# PCB-VU-SE-2.net
KiCad netlist of a schematic drawn in EAGLE
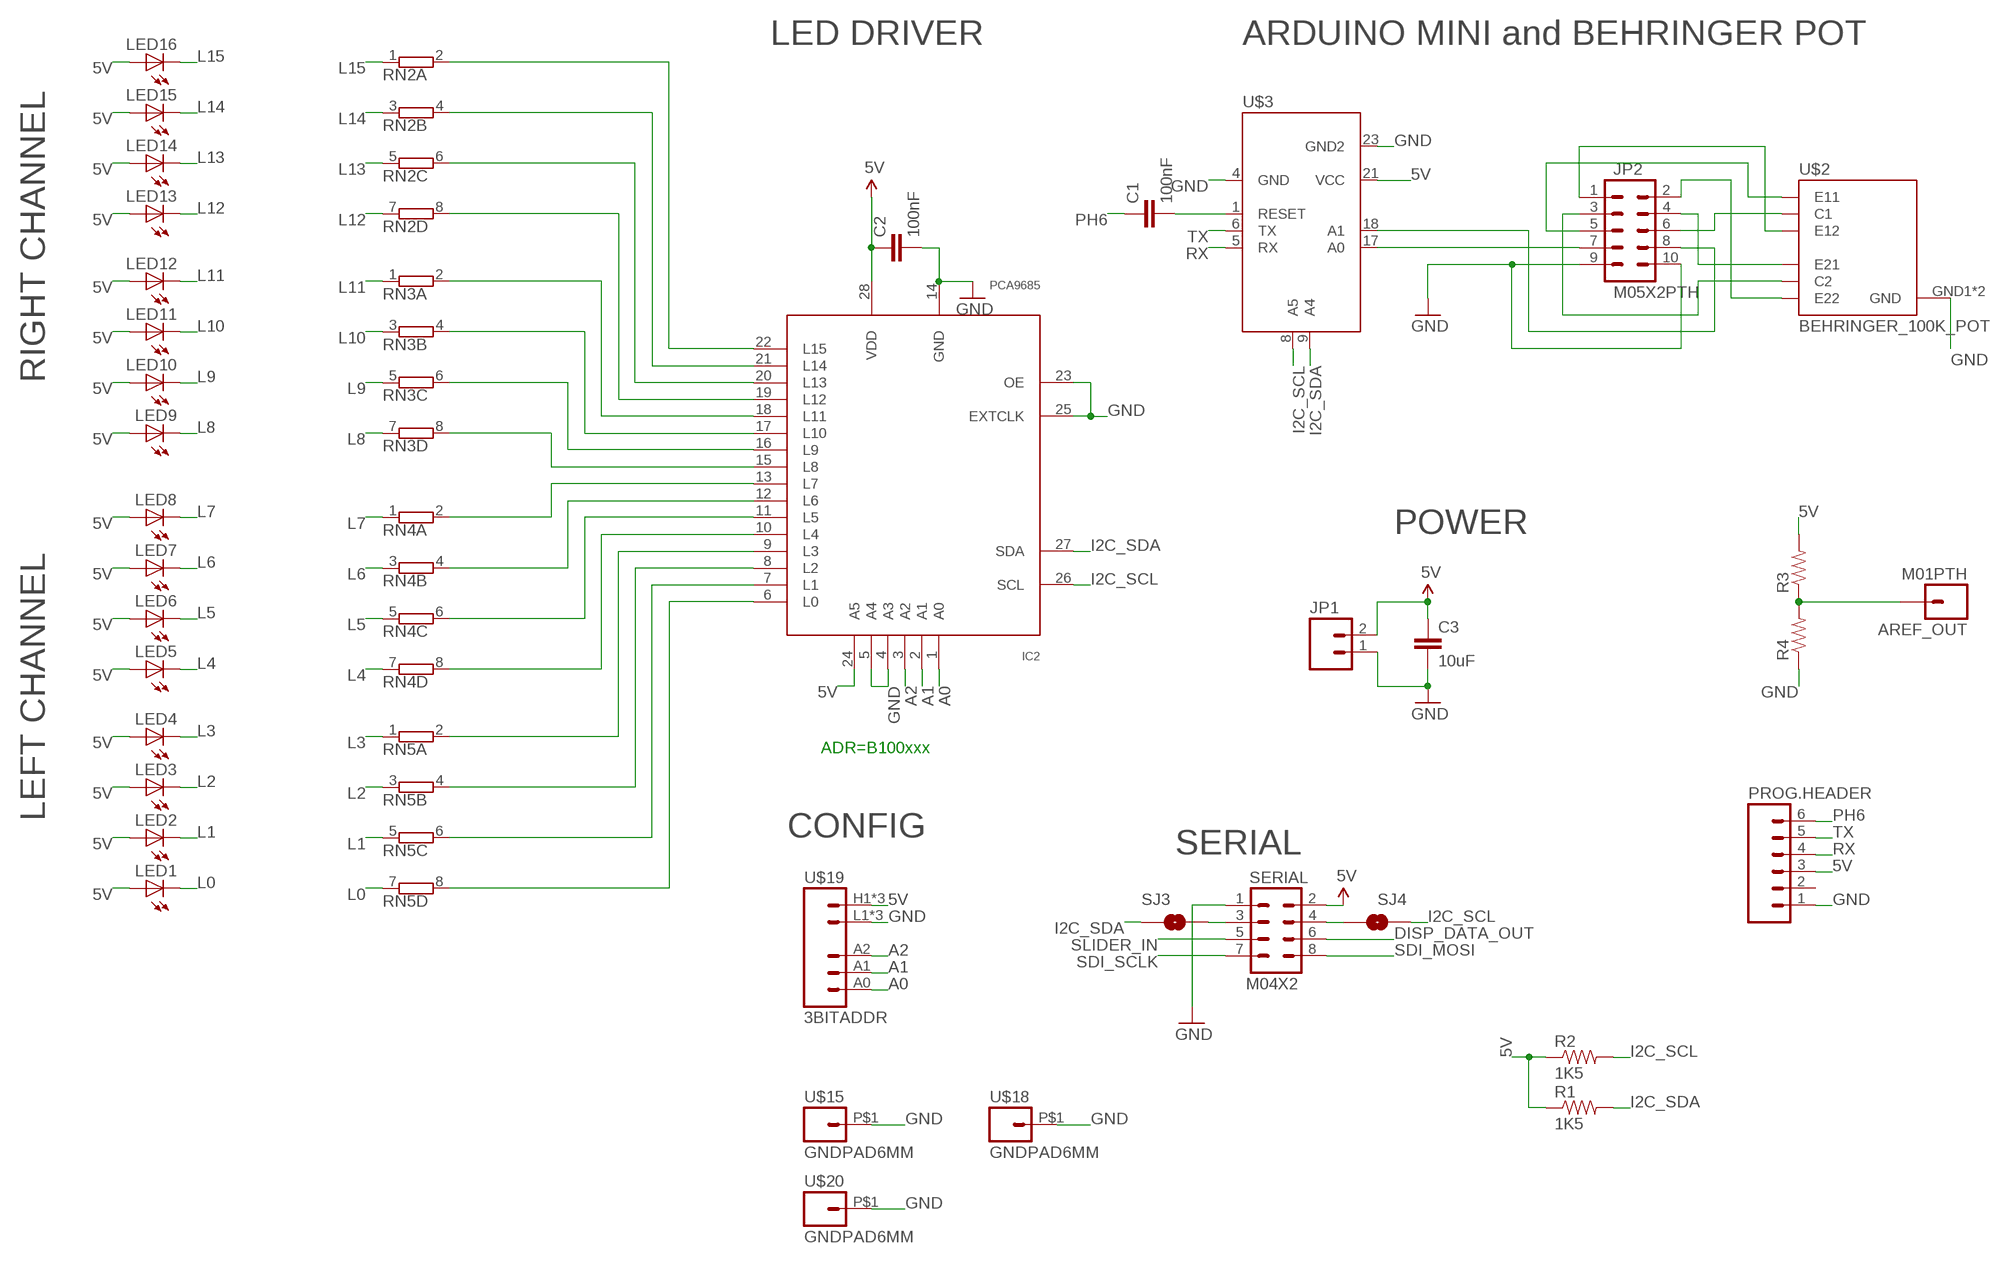
[diagram p0: schematic, sheet 1]

(export (version "E")
  (design (tool "Eeschema 10.0.6"))
  (components
    (comp (ref "AREF_OUT")
      (value "M01PTH")
      (footprint "eagle-import:1X01")
      (libsource (lib "eagle-import") (part "M01PTH"))
    )
    (comp (ref "C1")
      (value "100nF")
      (footprint "eagle-import:0603-CAP")
      (libsource (lib "eagle-import") (part "CAP0603-CAP"))
    )
    (comp (ref "C2")
      (value "100nF")
      (footprint "eagle-import:0603-CAP")
      (libsource (lib "eagle-import") (part "CAP0603-CAP"))
    )
    (comp (ref "C3")
      (value "10uF")
      (footprint "eagle-import:0805")
      (libsource (lib "eagle-import") (part "CAP0805"))
    )
    (comp (ref "IC2")
      (value "PCA9685")
      (footprint "eagle-import:TSSOP28")
      (libsource (lib "eagle-import") (part "PCA9685"))
    )
    (comp (ref "JP1")
      (value "M02PTH")
      (footprint "eagle-import:1X02")
      (libsource (lib "eagle-import") (part "M02PTH"))
    )
    (comp (ref "JP2")
      (value "M05X2PTH")
      (footprint "eagle-import:AVR_ICSP")
      (libsource (lib "eagle-import") (part "M05X2PTH"))
    )
    (comp (ref "LED1")
      (value "LED3MM")
      (footprint "eagle-import:LED3MM")
      (libsource (lib "eagle-import") (part "LED3MM"))
    )
    (comp (ref "LED2")
      (value "LED3MM")
      (footprint "eagle-import:LED3MM")
      (libsource (lib "eagle-import") (part "LED3MM"))
    )
    (comp (ref "LED3")
      (value "LED3MM")
      (footprint "eagle-import:LED3MM")
      (libsource (lib "eagle-import") (part "LED3MM"))
    )
    (comp (ref "LED4")
      (value "LED3MM")
      (footprint "eagle-import:LED3MM")
      (libsource (lib "eagle-import") (part "LED3MM"))
    )
    (comp (ref "LED5")
      (value "LED3MM")
      (footprint "eagle-import:LED3MM")
      (libsource (lib "eagle-import") (part "LED3MM"))
    )
    (comp (ref "LED6")
      (value "LED3MM")
      (footprint "eagle-import:LED3MM")
      (libsource (lib "eagle-import") (part "LED3MM"))
    )
    (comp (ref "LED7")
      (value "LED3MM")
      (footprint "eagle-import:LED3MM")
      (libsource (lib "eagle-import") (part "LED3MM"))
    )
    (comp (ref "LED8")
      (value "LED3MM")
      (footprint "eagle-import:LED3MM")
      (libsource (lib "eagle-import") (part "LED3MM"))
    )
    (comp (ref "LED9")
      (value "LED3MM")
      (footprint "eagle-import:LED3MM")
      (libsource (lib "eagle-import") (part "LED3MM"))
    )
    (comp (ref "LED10")
      (value "LED3MM")
      (footprint "eagle-import:LED3MM")
      (libsource (lib "eagle-import") (part "LED3MM"))
    )
    (comp (ref "LED11")
      (value "LED3MM")
      (footprint "eagle-import:LED3MM")
      (libsource (lib "eagle-import") (part "LED3MM"))
    )
    (comp (ref "LED12")
      (value "LED3MM")
      (footprint "eagle-import:LED3MM")
      (libsource (lib "eagle-import") (part "LED3MM"))
    )
    (comp (ref "LED13")
      (value "LED3MM")
      (footprint "eagle-import:LED3MM")
      (libsource (lib "eagle-import") (part "LED3MM"))
    )
    (comp (ref "LED14")
      (value "LED3MM")
      (footprint "eagle-import:LED3MM")
      (libsource (lib "eagle-import") (part "LED3MM"))
    )
    (comp (ref "LED15")
      (value "LED3MM")
      (footprint "eagle-import:LED3MM")
      (libsource (lib "eagle-import") (part "LED3MM"))
    )
    (comp (ref "LED16")
      (value "LED3MM")
      (footprint "eagle-import:LED3MM")
      (libsource (lib "eagle-import") (part "LED3MM"))
    )
    (comp (ref "PROG.HEADER")
      (value "M06LOCK")
      (footprint "eagle-import:1X06_LOCK")
      (libsource (lib "eagle-import") (part "M06LOCK"))
    )
    (comp (ref "R1")
      (value "1K5")
      (footprint "eagle-import:0603-RES")
      (libsource (lib "eagle-import") (part "RESISTOR0603-RES"))
    )
    (comp (ref "R2")
      (value "1K5")
      (footprint "eagle-import:0603-RES")
      (libsource (lib "eagle-import") (part "RESISTOR0603-RES"))
    )
    (comp (ref "R3")
      (value "RESISTOR0603-RES")
      (footprint "eagle-import:0603-RES")
      (libsource (lib "eagle-import") (part "RESISTOR0603-RES"))
    )
    (comp (ref "R4")
      (value "RESISTOR0603-RES")
      (footprint "eagle-import:0603-RES")
      (libsource (lib "eagle-import") (part "RESISTOR0603-RES"))
    )
    (comp (ref "RN2")
      (value "E4R")
      (footprint "eagle-import:SIL8")
      (libsource (lib "eagle-import") (part "E4R"))
    )
    (comp (ref "RN3")
      (value "E4R")
      (footprint "eagle-import:SIL8")
      (libsource (lib "eagle-import") (part "E4R"))
    )
    (comp (ref "RN4")
      (value "E4R")
      (footprint "eagle-import:SIL8")
      (libsource (lib "eagle-import") (part "E4R"))
    )
    (comp (ref "RN5")
      (value "E4R")
      (footprint "eagle-import:SIL8")
      (libsource (lib "eagle-import") (part "E4R"))
    )
    (comp (ref "SERIAL")
      (value "M04X2")
      (footprint "eagle-import:2X4")
      (libsource (lib "eagle-import") (part "M04X2"))
    )
    (comp (ref "SJ3")
      (value "SOLDERJUMPERNC")
      (footprint "eagle-import:SJ_2S")
      (libsource (lib "eagle-import") (part "SOLDERJUMPERNC"))
    )
    (comp (ref "SJ4")
      (value "SOLDERJUMPERNC")
      (footprint "eagle-import:SJ_2S")
      (libsource (lib "eagle-import") (part "SOLDERJUMPERNC"))
    )
    (comp (ref "U$2")
      (value "BEHRINGER_100K_POT")
      (footprint "eagle-import:BEHRINGER_100K_POT")
      (libsource (lib "eagle-import") (part "BEHRINGER_100K_POT"))
    )
    (comp (ref "U$3")
      (value "ARDUINO_MINI_SE1")
      (footprint "eagle-import:ARDUINO_MINI_SE1")
      (libsource (lib "eagle-import") (part "ARDUINO_MINI_SE1"))
    )
    (comp (ref "U$15")
      (value "GNDPAD6MM")
      (footprint "eagle-import:3.2MMPAD6MM")
      (libsource (lib "eagle-import") (part "GNDPAD6MM"))
    )
    (comp (ref "U$18")
      (value "GNDPAD6MM")
      (footprint "eagle-import:3.2MMPAD6MM")
      (libsource (lib "eagle-import") (part "GNDPAD6MM"))
    )
    (comp (ref "U$19")
      (value "3BITADDR")
      (footprint "eagle-import:3BITADDR")
      (libsource (lib "eagle-import") (part "3BITADDR"))
    )
    (comp (ref "U$20")
      (value "GNDPAD6MM")
      (footprint "eagle-import:3.2MMPAD6MM")
      (libsource (lib "eagle-import") (part "GNDPAD6MM"))
    )
  )
  (nets
    (net (code "1") (name "/A0") (class "Default")
      (node (ref "IC2") (pin "1") (pinfunction "A0_1") (pintype "input"))
      (node (ref "U$19") (pin "A0") (pinfunction "A0_A0") (pintype "passive"))
    )
    (net (code "2") (name "/A1") (class "Default")
      (node (ref "IC2") (pin "2") (pinfunction "A1_2") (pintype "input"))
      (node (ref "U$19") (pin "A1") (pinfunction "A1_A1") (pintype "passive"))
    )
    (net (code "3") (name "/A2") (class "Default")
      (node (ref "IC2") (pin "3") (pinfunction "A2_3") (pintype "input"))
      (node (ref "U$19") (pin "A2") (pinfunction "A2_A2") (pintype "passive"))
    )
    (net (code "4") (name "/DISP_DATA_OUT") (class "Default")
      (node (ref "SERIAL") (pin "6") (pinfunction "6_6") (pintype "passive"))
    )
    (net (code "5") (name "/I2C_SCL") (class "Default")
      (node (ref "IC2") (pin "26") (pinfunction "SCL_26") (pintype "input"))
      (node (ref "R2") (pin "2") (pinfunction "2_2") (pintype "passive"))
      (node (ref "SJ4") (pin "2") (pinfunction "2_2") (pintype "passive"))
      (node (ref "U$3") (pin "8") (pinfunction "A5_8") (pintype "bidirectional"))
    )
    (net (code "6") (name "/I2C_SDA") (class "Default")
      (node (ref "IC2") (pin "27") (pinfunction "SDA_27") (pintype "input"))
      (node (ref "R1") (pin "2") (pinfunction "2_2") (pintype "passive"))
      (node (ref "SJ3") (pin "1") (pinfunction "1_1") (pintype "passive"))
      (node (ref "U$3") (pin "9") (pinfunction "A4_9") (pintype "bidirectional"))
    )
    (net (code "7") (name "/L0") (class "Default")
      (node (ref "LED1") (pin "K") (pinfunction "C_K") (pintype "passive"))
      (node (ref "RN5") (pin "7") (pinfunction "1_7") (pintype "passive"))
    )
    (net (code "8") (name "/L1") (class "Default")
      (node (ref "LED2") (pin "K") (pinfunction "C_K") (pintype "passive"))
      (node (ref "RN5") (pin "5") (pinfunction "1_5") (pintype "passive"))
    )
    (net (code "9") (name "/L2") (class "Default")
      (node (ref "LED3") (pin "K") (pinfunction "C_K") (pintype "passive"))
      (node (ref "RN5") (pin "3") (pinfunction "1_3") (pintype "passive"))
    )
    (net (code "10") (name "/L3") (class "Default")
      (node (ref "LED4") (pin "K") (pinfunction "C_K") (pintype "passive"))
      (node (ref "RN5") (pin "1") (pinfunction "1_1") (pintype "passive"))
    )
    (net (code "11") (name "/L4") (class "Default")
      (node (ref "LED5") (pin "K") (pinfunction "C_K") (pintype "passive"))
      (node (ref "RN4") (pin "7") (pinfunction "1_7") (pintype "passive"))
    )
    (net (code "12") (name "/L5") (class "Default")
      (node (ref "LED6") (pin "K") (pinfunction "C_K") (pintype "passive"))
      (node (ref "RN4") (pin "5") (pinfunction "1_5") (pintype "passive"))
    )
    (net (code "13") (name "/L6") (class "Default")
      (node (ref "LED7") (pin "K") (pinfunction "C_K") (pintype "passive"))
      (node (ref "RN4") (pin "3") (pinfunction "1_3") (pintype "passive"))
    )
    (net (code "14") (name "/L7") (class "Default")
      (node (ref "LED8") (pin "K") (pinfunction "C_K") (pintype "passive"))
      (node (ref "RN4") (pin "1") (pinfunction "1_1") (pintype "passive"))
    )
    (net (code "15") (name "/L8") (class "Default")
      (node (ref "LED9") (pin "K") (pinfunction "C_K") (pintype "passive"))
      (node (ref "RN3") (pin "7") (pinfunction "1_7") (pintype "passive"))
    )
    (net (code "16") (name "/L9") (class "Default")
      (node (ref "LED10") (pin "K") (pinfunction "C_K") (pintype "passive"))
      (node (ref "RN3") (pin "5") (pinfunction "1_5") (pintype "passive"))
    )
    (net (code "17") (name "/L10") (class "Default")
      (node (ref "LED11") (pin "K") (pinfunction "C_K") (pintype "passive"))
      (node (ref "RN3") (pin "3") (pinfunction "1_3") (pintype "passive"))
    )
    (net (code "18") (name "/L11") (class "Default")
      (node (ref "LED12") (pin "K") (pinfunction "C_K") (pintype "passive"))
      (node (ref "RN3") (pin "1") (pinfunction "1_1") (pintype "passive"))
    )
    (net (code "19") (name "/L12") (class "Default")
      (node (ref "LED13") (pin "K") (pinfunction "C_K") (pintype "passive"))
      (node (ref "RN2") (pin "7") (pinfunction "1_7") (pintype "passive"))
    )
    (net (code "20") (name "/L13") (class "Default")
      (node (ref "LED14") (pin "K") (pinfunction "C_K") (pintype "passive"))
      (node (ref "RN2") (pin "5") (pinfunction "1_5") (pintype "passive"))
    )
    (net (code "21") (name "/L14") (class "Default")
      (node (ref "LED15") (pin "K") (pinfunction "C_K") (pintype "passive"))
      (node (ref "RN2") (pin "3") (pinfunction "1_3") (pintype "passive"))
    )
    (net (code "22") (name "/L15") (class "Default")
      (node (ref "LED16") (pin "K") (pinfunction "C_K") (pintype "passive"))
      (node (ref "RN2") (pin "1") (pinfunction "1_1") (pintype "passive"))
    )
    (net (code "23") (name "/PH6") (class "Default")
      (node (ref "C1") (pin "1") (pinfunction "1_1") (pintype "passive"))
      (node (ref "PROG.HEADER") (pin "6") (pinfunction "6_6") (pintype "passive"))
    )
    (net (code "24") (name "/RX") (class "Default")
      (node (ref "PROG.HEADER") (pin "4") (pinfunction "4_4") (pintype "passive"))
      (node (ref "U$3") (pin "5") (pinfunction "RX_5") (pintype "bidirectional"))
    )
    (net (code "25") (name "/SDI_MOSI") (class "Default")
      (node (ref "SERIAL") (pin "8") (pinfunction "8_8") (pintype "passive"))
    )
    (net (code "26") (name "/SDI_SCLK") (class "Default")
      (node (ref "SERIAL") (pin "7") (pinfunction "7_7") (pintype "passive"))
    )
    (net (code "27") (name "/SLIDER_IN") (class "Default")
      (node (ref "SERIAL") (pin "5") (pinfunction "5_5") (pintype "passive"))
    )
    (net (code "28") (name "/TX") (class "Default")
      (node (ref "PROG.HEADER") (pin "5") (pinfunction "5_5") (pintype "passive"))
      (node (ref "U$3") (pin "6") (pinfunction "TX_6") (pintype "bidirectional"))
    )
    (net (code "29") (name "5V") (class "Default")
      (node (ref "C2") (pin "1") (pinfunction "1_1") (pintype "passive"))
      (node (ref "C3") (pin "1") (pinfunction "1_1") (pintype "passive"))
      (node (ref "IC2") (pin "24") (pinfunction "A5_24") (pintype "input"))
      (node (ref "IC2") (pin "28") (pinfunction "VDD_28") (pintype "power_in"))
      (node (ref "JP1") (pin "2") (pinfunction "2_2") (pintype "passive"))
      (node (ref "LED1") (pin "A") (pinfunction "A_A") (pintype "passive"))
      (node (ref "LED10") (pin "A") (pinfunction "A_A") (pintype "passive"))
      (node (ref "LED11") (pin "A") (pinfunction "A_A") (pintype "passive"))
      (node (ref "LED12") (pin "A") (pinfunction "A_A") (pintype "passive"))
      (node (ref "LED13") (pin "A") (pinfunction "A_A") (pintype "passive"))
      (node (ref "LED14") (pin "A") (pinfunction "A_A") (pintype "passive"))
      (node (ref "LED15") (pin "A") (pinfunction "A_A") (pintype "passive"))
      (node (ref "LED16") (pin "A") (pinfunction "A_A") (pintype "passive"))
      (node (ref "LED2") (pin "A") (pinfunction "A_A") (pintype "passive"))
      (node (ref "LED3") (pin "A") (pinfunction "A_A") (pintype "passive"))
      (node (ref "LED4") (pin "A") (pinfunction "A_A") (pintype "passive"))
      (node (ref "LED5") (pin "A") (pinfunction "A_A") (pintype "passive"))
      (node (ref "LED6") (pin "A") (pinfunction "A_A") (pintype "passive"))
      (node (ref "LED7") (pin "A") (pinfunction "A_A") (pintype "passive"))
      (node (ref "LED8") (pin "A") (pinfunction "A_A") (pintype "passive"))
      (node (ref "LED9") (pin "A") (pinfunction "A_A") (pintype "passive"))
      (node (ref "PROG.HEADER") (pin "3") (pinfunction "3_3") (pintype "passive"))
      (node (ref "R1") (pin "1") (pinfunction "1_1") (pintype "passive"))
      (node (ref "R2") (pin "1") (pinfunction "1_1") (pintype "passive"))
      (node (ref "R3") (pin "2") (pinfunction "2_2") (pintype "passive"))
      (node (ref "SERIAL") (pin "2") (pinfunction "2_2") (pintype "passive"))
      (node (ref "U$19") (pin "H1") (pinfunction "VCC_H1") (pintype "passive"))
      (node (ref "U$19") (pin "H2") (pinfunction "VCC_H2") (pintype "passive"))
      (node (ref "U$19") (pin "H3") (pinfunction "VCC_H3") (pintype "passive"))
      (node (ref "U$3") (pin "21") (pinfunction "VCC_21") (pintype "bidirectional"))
    )
    (net (code "30") (name "GND") (class "Default")
      (node (ref "C2") (pin "2") (pinfunction "2_2") (pintype "passive"))
      (node (ref "C3") (pin "2") (pinfunction "2_2") (pintype "passive"))
      (node (ref "IC2") (pin "14") (pinfunction "GND_14") (pintype "power_in"))
      (node (ref "IC2") (pin "23") (pinfunction "OE_23") (pintype "input"))
      (node (ref "IC2") (pin "25") (pinfunction "EXTCLK_25") (pintype "input"))
      (node (ref "IC2") (pin "4") (pinfunction "A3_4") (pintype "input"))
      (node (ref "IC2") (pin "5") (pinfunction "A4_5") (pintype "input"))
      (node (ref "JP1") (pin "1") (pinfunction "1_1") (pintype "passive"))
      (node (ref "JP2") (pin "10") (pinfunction "10_10") (pintype "passive"))
      (node (ref "JP2") (pin "9") (pinfunction "9_9") (pintype "passive"))
      (node (ref "PROG.HEADER") (pin "1") (pinfunction "1_1") (pintype "passive"))
      (node (ref "R4") (pin "1") (pinfunction "1_1") (pintype "passive"))
      (node (ref "SERIAL") (pin "1") (pinfunction "1_1") (pintype "passive"))
      (node (ref "U$15") (pin "P$1") (pinfunction "1_P$1") (pintype "passive"))
      (node (ref "U$18") (pin "P$1") (pinfunction "1_P$1") (pintype "passive"))
      (node (ref "U$19") (pin "L1") (pinfunction "GND_L1") (pintype "passive"))
      (node (ref "U$19") (pin "L2") (pinfunction "GND_L2") (pintype "passive"))
      (node (ref "U$19") (pin "L3") (pinfunction "GND_L3") (pintype "passive"))
      (node (ref "U$2") (pin "GND1") (pinfunction "GND_GND1") (pintype "power_in"))
      (node (ref "U$2") (pin "GND2") (pinfunction "GND_GND2") (pintype "power_in"))
      (node (ref "U$20") (pin "P$1") (pinfunction "1_P$1") (pintype "passive"))
      (node (ref "U$3") (pin "23") (pinfunction "GND2_23") (pintype "bidirectional"))
      (node (ref "U$3") (pin "4") (pinfunction "GND_4") (pintype "bidirectional"))
    )
    (net (code "31") (name "Net-(AREF_OUT-Pad1)") (class "Default")
      (node (ref "AREF_OUT") (pin "1") (pinfunction "1_1") (pintype "passive"))
      (node (ref "R3") (pin "1") (pinfunction "1_1") (pintype "passive"))
      (node (ref "R4") (pin "2") (pinfunction "2_2") (pintype "passive"))
    )
    (net (code "32") (name "Net-(IC2-L0)") (class "Default")
      (node (ref "IC2") (pin "6") (pinfunction "L0_6") (pintype "output"))
      (node (ref "RN5") (pin "8") (pinfunction "2_8") (pintype "passive"))
    )
    (net (code "33") (name "Net-(IC2-L1)") (class "Default")
      (node (ref "IC2") (pin "7") (pinfunction "L1_7") (pintype "output"))
      (node (ref "RN5") (pin "6") (pinfunction "2_6") (pintype "passive"))
    )
    (net (code "34") (name "Net-(IC2-L2)") (class "Default")
      (node (ref "IC2") (pin "8") (pinfunction "L2_8") (pintype "output"))
      (node (ref "RN5") (pin "4") (pinfunction "2_4") (pintype "passive"))
    )
    (net (code "35") (name "Net-(IC2-L3)") (class "Default")
      (node (ref "IC2") (pin "9") (pinfunction "L3_9") (pintype "output"))
      (node (ref "RN5") (pin "2") (pinfunction "2_2") (pintype "passive"))
    )
    (net (code "36") (name "Net-(IC2-L4)") (class "Default")
      (node (ref "IC2") (pin "10") (pinfunction "L4_10") (pintype "output"))
      (node (ref "RN4") (pin "8") (pinfunction "2_8") (pintype "passive"))
    )
    (net (code "37") (name "Net-(IC2-L5)") (class "Default")
      (node (ref "IC2") (pin "11") (pinfunction "L5_11") (pintype "output"))
      (node (ref "RN4") (pin "6") (pinfunction "2_6") (pintype "passive"))
    )
    (net (code "38") (name "Net-(IC2-L6)") (class "Default")
      (node (ref "IC2") (pin "12") (pinfunction "L6_12") (pintype "output"))
      (node (ref "RN4") (pin "4") (pinfunction "2_4") (pintype "passive"))
    )
    (net (code "39") (name "Net-(IC2-L7)") (class "Default")
      (node (ref "IC2") (pin "13") (pinfunction "L7_13") (pintype "output"))
      (node (ref "RN4") (pin "2") (pinfunction "2_2") (pintype "passive"))
    )
    (net (code "40") (name "Net-(IC2-L8)") (class "Default")
      (node (ref "IC2") (pin "15") (pinfunction "L8_15") (pintype "output"))
      (node (ref "RN3") (pin "8") (pinfunction "2_8") (pintype "passive"))
    )
    (net (code "41") (name "Net-(IC2-L9)") (class "Default")
      (node (ref "IC2") (pin "16") (pinfunction "L9_16") (pintype "output"))
      (node (ref "RN3") (pin "6") (pinfunction "2_6") (pintype "passive"))
    )
    (net (code "42") (name "Net-(IC2-L10)") (class "Default")
      (node (ref "IC2") (pin "17") (pinfunction "L10_17") (pintype "output"))
      (node (ref "RN3") (pin "4") (pinfunction "2_4") (pintype "passive"))
    )
    (net (code "43") (name "Net-(IC2-L11)") (class "Default")
      (node (ref "IC2") (pin "18") (pinfunction "L11_18") (pintype "output"))
      (node (ref "RN3") (pin "2") (pinfunction "2_2") (pintype "passive"))
    )
    (net (code "44") (name "Net-(IC2-L12)") (class "Default")
      (node (ref "IC2") (pin "19") (pinfunction "L12_19") (pintype "output"))
      (node (ref "RN2") (pin "8") (pinfunction "2_8") (pintype "passive"))
    )
    (net (code "45") (name "Net-(IC2-L13)") (class "Default")
      (node (ref "IC2") (pin "20") (pinfunction "L13_20") (pintype "output"))
      (node (ref "RN2") (pin "6") (pinfunction "2_6") (pintype "passive"))
    )
    (net (code "46") (name "Net-(IC2-L14)") (class "Default")
      (node (ref "IC2") (pin "21") (pinfunction "L14_21") (pintype "output"))
      (node (ref "RN2") (pin "4") (pinfunction "2_4") (pintype "passive"))
    )
    (net (code "47") (name "Net-(IC2-L15)") (class "Default")
      (node (ref "IC2") (pin "22") (pinfunction "L15_22") (pintype "output"))
      (node (ref "RN2") (pin "2") (pinfunction "2_2") (pintype "passive"))
    )
    (net (code "48") (name "Net-(SERIAL-Pad3)") (class "Default")
      (node (ref "SERIAL") (pin "3") (pinfunction "3_3") (pintype "passive"))
      (node (ref "SJ3") (pin "2") (pinfunction "2_2") (pintype "passive"))
    )
    (net (code "49") (name "Net-(SERIAL-Pad4)") (class "Default")
      (node (ref "SERIAL") (pin "4") (pinfunction "4_4") (pintype "passive"))
      (node (ref "SJ4") (pin "1") (pinfunction "1_1") (pintype "passive"))
    )
    (net (code "50") (name "Net-(U$2-C1)") (class "Default")
      (node (ref "JP2") (pin "6") (pinfunction "6_6") (pintype "passive"))
      (node (ref "U$2") (pin "PAD1") (pinfunction "C1_PAD1") (pintype "bidirectional"))
    )
    (net (code "51") (name "Net-(U$2-C2)") (class "Default")
      (node (ref "JP2") (pin "3") (pinfunction "3_3") (pintype "passive"))
      (node (ref "U$2") (pin "PAD4") (pinfunction "C2_PAD4") (pintype "bidirectional"))
    )
    (net (code "52") (name "Net-(U$2-E11)") (class "Default")
      (node (ref "JP2") (pin "5") (pinfunction "5_5") (pintype "passive"))
      (node (ref "U$2") (pin "PAD2") (pinfunction "E11_PAD2") (pintype "bidirectional"))
    )
    (net (code "53") (name "Net-(U$2-E12)") (class "Default")
      (node (ref "JP2") (pin "1") (pinfunction "1_1") (pintype "passive"))
      (node (ref "U$2") (pin "PAD6") (pinfunction "E12_PAD6") (pintype "bidirectional"))
    )
    (net (code "54") (name "Net-(U$2-E21)") (class "Default")
      (node (ref "JP2") (pin "4") (pinfunction "4_4") (pintype "passive"))
      (node (ref "U$2") (pin "PAD3") (pinfunction "E21_PAD3") (pintype "bidirectional"))
    )
    (net (code "55") (name "Net-(U$2-E22)") (class "Default")
      (node (ref "JP2") (pin "2") (pinfunction "2_2") (pintype "passive"))
      (node (ref "U$2") (pin "PAD5") (pinfunction "E22_PAD5") (pintype "bidirectional"))
    )
    (net (code "56") (name "Net-(U$3-A0)") (class "Default")
      (node (ref "JP2") (pin "7") (pinfunction "7_7") (pintype "passive"))
      (node (ref "U$3") (pin "17") (pinfunction "A0_17") (pintype "bidirectional"))
    )
    (net (code "57") (name "Net-(U$3-A1)") (class "Default")
      (node (ref "JP2") (pin "8") (pinfunction "8_8") (pintype "passive"))
      (node (ref "U$3") (pin "18") (pinfunction "A1_18") (pintype "bidirectional"))
    )
    (net (code "58") (name "Net-(U$3-RESET)") (class "Default")
      (node (ref "C1") (pin "2") (pinfunction "2_2") (pintype "passive"))
      (node (ref "U$3") (pin "1") (pinfunction "RESET_1") (pintype "bidirectional"))
    )
    (net (code "59") (name "unconnected-(PROG.HEADER-Pad2)") (class "Default")
      (node (ref "PROG.HEADER") (pin "2") (pinfunction "2_2") (pintype "passive"))
    )
  )
)
